# tiffany.net
KiCad netlist of a schematic drawn in EAGLE
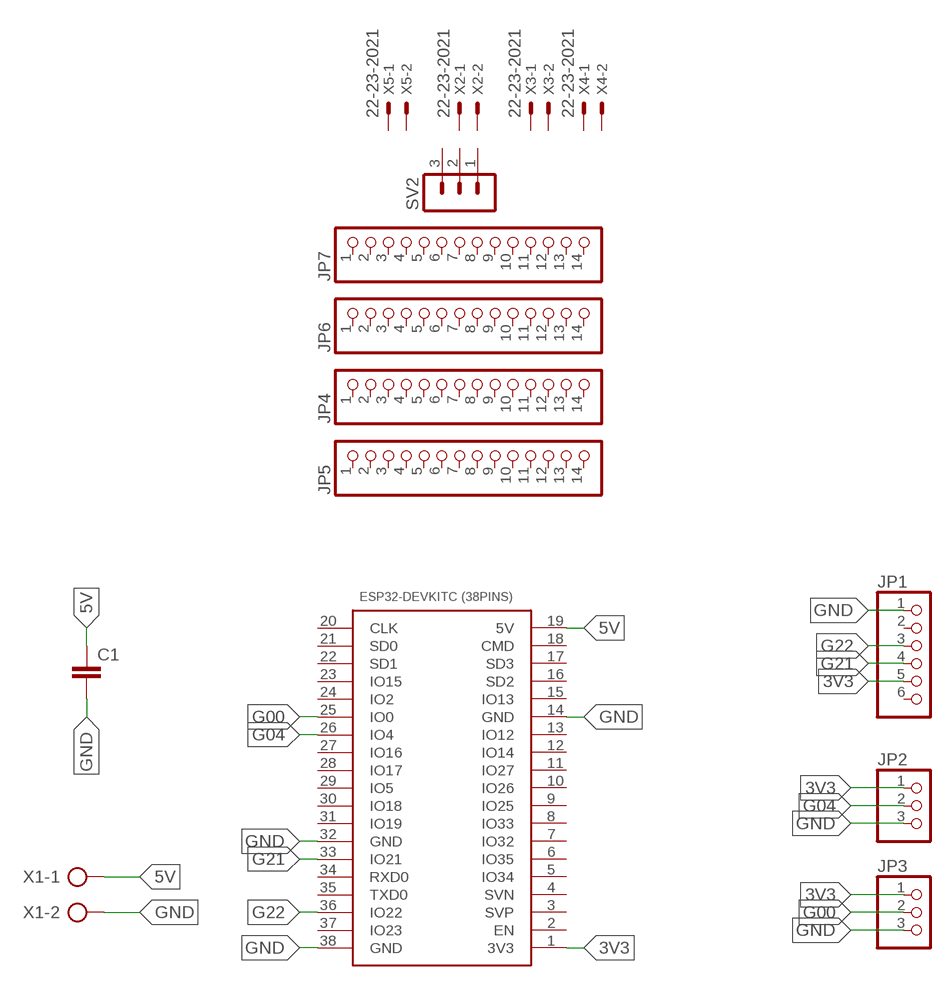
[diagram p0: schematic, sheet 1]

(export (version "E")
  (design (tool "Eeschema 10.0.6"))
  (components
    (comp (ref "C1")
      (value "C-EU050-024X044")
      (footprint "eagle-import:C050-024X044")
      (libsource (lib "eagle-import") (part "C-EU050-024X044"))
    )
    (comp (ref "ESP32-DEVKITC(38PINS)1")
      (value "ESP32DEVKITC_38PINS")
      (footprint "eagle-import:ESP32-DEVKITC")
      (libsource (lib "eagle-import") (part "ESP32DEVKITC_38PINS"))
    )
    (comp (ref "JP1")
      (value "PINHD-1X6")
      (footprint "eagle-import:1X06")
      (libsource (lib "eagle-import") (part "PINHD-1X6"))
    )
    (comp (ref "JP2")
      (value "PINHD-1X3")
      (footprint "eagle-import:1X03")
      (libsource (lib "eagle-import") (part "PINHD-1X3"))
    )
    (comp (ref "JP3")
      (value "PINHD-1X3")
      (footprint "eagle-import:1X03")
      (libsource (lib "eagle-import") (part "PINHD-1X3"))
    )
    (comp (ref "JP4")
      (value "PINHD-1X14")
      (footprint "eagle-import:1X14")
      (libsource (lib "eagle-import") (part "PINHD-1X14"))
    )
    (comp (ref "JP5")
      (value "PINHD-1X14")
      (footprint "eagle-import:1X14")
      (libsource (lib "eagle-import") (part "PINHD-1X14"))
    )
    (comp (ref "JP6")
      (value "PINHD-1X14")
      (footprint "eagle-import:1X14")
      (libsource (lib "eagle-import") (part "PINHD-1X14"))
    )
    (comp (ref "JP7")
      (value "PINHD-1X14")
      (footprint "eagle-import:1X14")
      (libsource (lib "eagle-import") (part "PINHD-1X14"))
    )
    (comp (ref "SV2")
      (value "MA03-1")
      (footprint "eagle-import:MA03-1")
      (libsource (lib "eagle-import") (part "MA03-1"))
    )
    (comp (ref "X1")
      (value "AK300/2")
      (footprint "eagle-import:AK300_2")
      (libsource (lib "eagle-import") (part "AK300/2"))
    )
    (comp (ref "X2")
      (value "22-23-2021")
      (footprint "eagle-import:22-23-2021")
      (fields (field (name "MF") "MOLEX"))
      (libsource (lib "eagle-import") (part "22-23-2021"))
    )
    (comp (ref "X3")
      (value "22-23-2021")
      (footprint "eagle-import:22-23-2021")
      (fields (field (name "MF") "MOLEX"))
      (libsource (lib "eagle-import") (part "22-23-2021"))
    )
    (comp (ref "X4")
      (value "22-23-2021")
      (footprint "eagle-import:22-23-2021")
      (fields (field (name "MF") "MOLEX"))
      (libsource (lib "eagle-import") (part "22-23-2021"))
    )
    (comp (ref "X5")
      (value "22-23-2021")
      (footprint "eagle-import:22-23-2021")
      (fields (field (name "MF") "MOLEX"))
      (libsource (lib "eagle-import") (part "22-23-2021"))
    )
  )
  (nets
    (net (code "1") (name "3V3") (class "Default")
      (node (ref "ESP32-DEVKITC(38PINS)1") (pin "1") (pinfunction "3V3_1") (pintype "bidirectional"))
      (node (ref "JP1") (pin "5") (pinfunction "5_5") (pintype "passive"))
      (node (ref "JP2") (pin "1") (pinfunction "1_1") (pintype "passive"))
      (node (ref "JP3") (pin "1") (pinfunction "1_1") (pintype "passive"))
    )
    (net (code "2") (name "5V") (class "Default")
      (node (ref "C1") (pin "1") (pinfunction "1_1") (pintype "passive"))
      (node (ref "ESP32-DEVKITC(38PINS)1") (pin "19") (pinfunction "5V_19") (pintype "bidirectional"))
      (node (ref "X1") (pin "1") (pinfunction "KL_1") (pintype "passive"))
    )
    (net (code "3") (name "G00") (class "Default")
      (node (ref "ESP32-DEVKITC(38PINS)1") (pin "25") (pinfunction "IO0_25") (pintype "bidirectional"))
      (node (ref "JP3") (pin "2") (pinfunction "2_2") (pintype "passive"))
    )
    (net (code "4") (name "G04") (class "Default")
      (node (ref "ESP32-DEVKITC(38PINS)1") (pin "26") (pinfunction "IO4_26") (pintype "bidirectional"))
      (node (ref "JP2") (pin "2") (pinfunction "2_2") (pintype "passive"))
    )
    (net (code "5") (name "G21") (class "Default")
      (node (ref "ESP32-DEVKITC(38PINS)1") (pin "33") (pinfunction "IO21_33") (pintype "bidirectional"))
      (node (ref "JP1") (pin "4") (pinfunction "4_4") (pintype "passive"))
    )
    (net (code "6") (name "G22") (class "Default")
      (node (ref "ESP32-DEVKITC(38PINS)1") (pin "36") (pinfunction "IO22_36") (pintype "bidirectional"))
      (node (ref "JP1") (pin "3") (pinfunction "3_3") (pintype "passive"))
    )
    (net (code "7") (name "GND") (class "Default")
      (node (ref "C1") (pin "2") (pinfunction "2_2") (pintype "passive"))
      (node (ref "ESP32-DEVKITC(38PINS)1") (pin "14") (pinfunction "GND_14") (pintype "bidirectional"))
      (node (ref "ESP32-DEVKITC(38PINS)1") (pin "32") (pinfunction "GND_32") (pintype "bidirectional"))
      (node (ref "ESP32-DEVKITC(38PINS)1") (pin "38") (pinfunction "GND_38") (pintype "bidirectional"))
      (node (ref "JP1") (pin "1") (pinfunction "1_1") (pintype "passive"))
      (node (ref "JP2") (pin "3") (pinfunction "3_3") (pintype "passive"))
      (node (ref "JP3") (pin "3") (pinfunction "3_3") (pintype "passive"))
      (node (ref "X1") (pin "2") (pinfunction "KL_2") (pintype "passive"))
    )
    (net (code "8") (name "unconnected-(ESP32-DEVKITC(38PINS)1-CLK-Pad20)") (class "Default")
      (node (ref "ESP32-DEVKITC(38PINS)1") (pin "20") (pinfunction "CLK_20") (pintype "bidirectional"))
    )
    (net (code "9") (name "unconnected-(ESP32-DEVKITC(38PINS)1-CMD-Pad18)") (class "Default")
      (node (ref "ESP32-DEVKITC(38PINS)1") (pin "18") (pinfunction "CMD_18") (pintype "bidirectional"))
    )
    (net (code "10") (name "unconnected-(ESP32-DEVKITC(38PINS)1-EN-Pad2)") (class "Default")
      (node (ref "ESP32-DEVKITC(38PINS)1") (pin "2") (pinfunction "EN_2") (pintype "bidirectional"))
    )
    (net (code "11") (name "unconnected-(ESP32-DEVKITC(38PINS)1-IO2-Pad24)") (class "Default")
      (node (ref "ESP32-DEVKITC(38PINS)1") (pin "24") (pinfunction "IO2_24") (pintype "bidirectional"))
    )
    (net (code "12") (name "unconnected-(ESP32-DEVKITC(38PINS)1-IO5-Pad29)") (class "Default")
      (node (ref "ESP32-DEVKITC(38PINS)1") (pin "29") (pinfunction "IO5_29") (pintype "bidirectional"))
    )
    (net (code "13") (name "unconnected-(ESP32-DEVKITC(38PINS)1-IO12-Pad13)") (class "Default")
      (node (ref "ESP32-DEVKITC(38PINS)1") (pin "13") (pinfunction "IO12_13") (pintype "bidirectional"))
    )
    (net (code "14") (name "unconnected-(ESP32-DEVKITC(38PINS)1-IO13-Pad15)") (class "Default")
      (node (ref "ESP32-DEVKITC(38PINS)1") (pin "15") (pinfunction "IO13_15") (pintype "bidirectional"))
    )
    (net (code "15") (name "unconnected-(ESP32-DEVKITC(38PINS)1-IO14-Pad12)") (class "Default")
      (node (ref "ESP32-DEVKITC(38PINS)1") (pin "12") (pinfunction "IO14_12") (pintype "bidirectional"))
    )
    (net (code "16") (name "unconnected-(ESP32-DEVKITC(38PINS)1-IO15-Pad23)") (class "Default")
      (node (ref "ESP32-DEVKITC(38PINS)1") (pin "23") (pinfunction "IO15_23") (pintype "bidirectional"))
    )
    (net (code "17") (name "unconnected-(ESP32-DEVKITC(38PINS)1-IO16-Pad27)") (class "Default")
      (node (ref "ESP32-DEVKITC(38PINS)1") (pin "27") (pinfunction "IO16_27") (pintype "bidirectional"))
    )
    (net (code "18") (name "unconnected-(ESP32-DEVKITC(38PINS)1-IO17-Pad28)") (class "Default")
      (node (ref "ESP32-DEVKITC(38PINS)1") (pin "28") (pinfunction "IO17_28") (pintype "bidirectional"))
    )
    (net (code "19") (name "unconnected-(ESP32-DEVKITC(38PINS)1-IO18-Pad30)") (class "Default")
      (node (ref "ESP32-DEVKITC(38PINS)1") (pin "30") (pinfunction "IO18_30") (pintype "bidirectional"))
    )
    (net (code "20") (name "unconnected-(ESP32-DEVKITC(38PINS)1-IO19-Pad31)") (class "Default")
      (node (ref "ESP32-DEVKITC(38PINS)1") (pin "31") (pinfunction "IO19_31") (pintype "bidirectional"))
    )
    (net (code "21") (name "unconnected-(ESP32-DEVKITC(38PINS)1-IO23-Pad37)") (class "Default")
      (node (ref "ESP32-DEVKITC(38PINS)1") (pin "37") (pinfunction "IO23_37") (pintype "bidirectional"))
    )
    (net (code "22") (name "unconnected-(ESP32-DEVKITC(38PINS)1-IO25-Pad9)") (class "Default")
      (node (ref "ESP32-DEVKITC(38PINS)1") (pin "9") (pinfunction "IO25_9") (pintype "bidirectional"))
    )
    (net (code "23") (name "unconnected-(ESP32-DEVKITC(38PINS)1-IO26-Pad10)") (class "Default")
      (node (ref "ESP32-DEVKITC(38PINS)1") (pin "10") (pinfunction "IO26_10") (pintype "bidirectional"))
    )
    (net (code "24") (name "unconnected-(ESP32-DEVKITC(38PINS)1-IO27-Pad11)") (class "Default")
      (node (ref "ESP32-DEVKITC(38PINS)1") (pin "11") (pinfunction "IO27_11") (pintype "bidirectional"))
    )
    (net (code "25") (name "unconnected-(ESP32-DEVKITC(38PINS)1-IO32-Pad7)") (class "Default")
      (node (ref "ESP32-DEVKITC(38PINS)1") (pin "7") (pinfunction "IO32_7") (pintype "bidirectional"))
    )
    (net (code "26") (name "unconnected-(ESP32-DEVKITC(38PINS)1-IO33-Pad8)") (class "Default")
      (node (ref "ESP32-DEVKITC(38PINS)1") (pin "8") (pinfunction "IO33_8") (pintype "bidirectional"))
    )
    (net (code "27") (name "unconnected-(ESP32-DEVKITC(38PINS)1-IO34-Pad5)") (class "Default")
      (node (ref "ESP32-DEVKITC(38PINS)1") (pin "5") (pinfunction "IO34_5") (pintype "bidirectional"))
    )
    (net (code "28") (name "unconnected-(ESP32-DEVKITC(38PINS)1-IO35-Pad6)") (class "Default")
      (node (ref "ESP32-DEVKITC(38PINS)1") (pin "6") (pinfunction "IO35_6") (pintype "bidirectional"))
    )
    (net (code "29") (name "unconnected-(ESP32-DEVKITC(38PINS)1-RXD0-Pad34)") (class "Default")
      (node (ref "ESP32-DEVKITC(38PINS)1") (pin "34") (pinfunction "RXD0_34") (pintype "bidirectional"))
    )
    (net (code "30") (name "unconnected-(ESP32-DEVKITC(38PINS)1-SD0-Pad21)") (class "Default")
      (node (ref "ESP32-DEVKITC(38PINS)1") (pin "21") (pinfunction "SD0_21") (pintype "bidirectional"))
    )
    (net (code "31") (name "unconnected-(ESP32-DEVKITC(38PINS)1-SD1-Pad22)") (class "Default")
      (node (ref "ESP32-DEVKITC(38PINS)1") (pin "22") (pinfunction "SD1_22") (pintype "bidirectional"))
    )
    (net (code "32") (name "unconnected-(ESP32-DEVKITC(38PINS)1-SD2-Pad16)") (class "Default")
      (node (ref "ESP32-DEVKITC(38PINS)1") (pin "16") (pinfunction "SD2_16") (pintype "bidirectional"))
    )
    (net (code "33") (name "unconnected-(ESP32-DEVKITC(38PINS)1-SD3-Pad17)") (class "Default")
      (node (ref "ESP32-DEVKITC(38PINS)1") (pin "17") (pinfunction "SD3_17") (pintype "bidirectional"))
    )
    (net (code "34") (name "unconnected-(ESP32-DEVKITC(38PINS)1-SVN-Pad4)") (class "Default")
      (node (ref "ESP32-DEVKITC(38PINS)1") (pin "4") (pinfunction "SVN_4") (pintype "bidirectional"))
    )
    (net (code "35") (name "unconnected-(ESP32-DEVKITC(38PINS)1-SVP-Pad3)") (class "Default")
      (node (ref "ESP32-DEVKITC(38PINS)1") (pin "3") (pinfunction "SVP_3") (pintype "bidirectional"))
    )
    (net (code "36") (name "unconnected-(ESP32-DEVKITC(38PINS)1-TXD0-Pad35)") (class "Default")
      (node (ref "ESP32-DEVKITC(38PINS)1") (pin "35") (pinfunction "TXD0_35") (pintype "bidirectional"))
    )
    (net (code "37") (name "unconnected-(JP1-Pad2)") (class "Default")
      (node (ref "JP1") (pin "2") (pinfunction "2_2") (pintype "passive"))
    )
    (net (code "38") (name "unconnected-(JP1-Pad6)") (class "Default")
      (node (ref "JP1") (pin "6") (pinfunction "6_6") (pintype "passive"))
    )
    (net (code "39") (name "unconnected-(JP4-Pad1)") (class "Default")
      (node (ref "JP4") (pin "1") (pinfunction "1_1") (pintype "passive"))
    )
    (net (code "40") (name "unconnected-(JP4-Pad2)") (class "Default")
      (node (ref "JP4") (pin "2") (pinfunction "2_2") (pintype "passive"))
    )
    (net (code "41") (name "unconnected-(JP4-Pad3)") (class "Default")
      (node (ref "JP4") (pin "3") (pinfunction "3_3") (pintype "passive"))
    )
    (net (code "42") (name "unconnected-(JP4-Pad4)") (class "Default")
      (node (ref "JP4") (pin "4") (pinfunction "4_4") (pintype "passive"))
    )
    (net (code "43") (name "unconnected-(JP4-Pad5)") (class "Default")
      (node (ref "JP4") (pin "5") (pinfunction "5_5") (pintype "passive"))
    )
    (net (code "44") (name "unconnected-(JP4-Pad6)") (class "Default")
      (node (ref "JP4") (pin "6") (pinfunction "6_6") (pintype "passive"))
    )
    (net (code "45") (name "unconnected-(JP4-Pad7)") (class "Default")
      (node (ref "JP4") (pin "7") (pinfunction "7_7") (pintype "passive"))
    )
    (net (code "46") (name "unconnected-(JP4-Pad8)") (class "Default")
      (node (ref "JP4") (pin "8") (pinfunction "8_8") (pintype "passive"))
    )
    (net (code "47") (name "unconnected-(JP4-Pad9)") (class "Default")
      (node (ref "JP4") (pin "9") (pinfunction "9_9") (pintype "passive"))
    )
    (net (code "48") (name "unconnected-(JP4-Pad10)") (class "Default")
      (node (ref "JP4") (pin "10") (pinfunction "10_10") (pintype "passive"))
    )
    (net (code "49") (name "unconnected-(JP4-Pad11)") (class "Default")
      (node (ref "JP4") (pin "11") (pinfunction "11_11") (pintype "passive"))
    )
    (net (code "50") (name "unconnected-(JP4-Pad12)") (class "Default")
      (node (ref "JP4") (pin "12") (pinfunction "12_12") (pintype "passive"))
    )
    (net (code "51") (name "unconnected-(JP4-Pad13)") (class "Default")
      (node (ref "JP4") (pin "13") (pinfunction "13_13") (pintype "passive"))
    )
    (net (code "52") (name "unconnected-(JP4-Pad14)") (class "Default")
      (node (ref "JP4") (pin "14") (pinfunction "14_14") (pintype "passive"))
    )
    (net (code "53") (name "unconnected-(JP5-Pad1)") (class "Default")
      (node (ref "JP5") (pin "1") (pinfunction "1_1") (pintype "passive"))
    )
    (net (code "54") (name "unconnected-(JP5-Pad2)") (class "Default")
      (node (ref "JP5") (pin "2") (pinfunction "2_2") (pintype "passive"))
    )
    (net (code "55") (name "unconnected-(JP5-Pad3)") (class "Default")
      (node (ref "JP5") (pin "3") (pinfunction "3_3") (pintype "passive"))
    )
    (net (code "56") (name "unconnected-(JP5-Pad4)") (class "Default")
      (node (ref "JP5") (pin "4") (pinfunction "4_4") (pintype "passive"))
    )
    (net (code "57") (name "unconnected-(JP5-Pad5)") (class "Default")
      (node (ref "JP5") (pin "5") (pinfunction "5_5") (pintype "passive"))
    )
    (net (code "58") (name "unconnected-(JP5-Pad6)") (class "Default")
      (node (ref "JP5") (pin "6") (pinfunction "6_6") (pintype "passive"))
    )
    (net (code "59") (name "unconnected-(JP5-Pad7)") (class "Default")
      (node (ref "JP5") (pin "7") (pinfunction "7_7") (pintype "passive"))
    )
    (net (code "60") (name "unconnected-(JP5-Pad8)") (class "Default")
      (node (ref "JP5") (pin "8") (pinfunction "8_8") (pintype "passive"))
    )
    (net (code "61") (name "unconnected-(JP5-Pad9)") (class "Default")
      (node (ref "JP5") (pin "9") (pinfunction "9_9") (pintype "passive"))
    )
    (net (code "62") (name "unconnected-(JP5-Pad10)") (class "Default")
      (node (ref "JP5") (pin "10") (pinfunction "10_10") (pintype "passive"))
    )
    (net (code "63") (name "unconnected-(JP5-Pad11)") (class "Default")
      (node (ref "JP5") (pin "11") (pinfunction "11_11") (pintype "passive"))
    )
    (net (code "64") (name "unconnected-(JP5-Pad12)") (class "Default")
      (node (ref "JP5") (pin "12") (pinfunction "12_12") (pintype "passive"))
    )
    (net (code "65") (name "unconnected-(JP5-Pad13)") (class "Default")
      (node (ref "JP5") (pin "13") (pinfunction "13_13") (pintype "passive"))
    )
    (net (code "66") (name "unconnected-(JP5-Pad14)") (class "Default")
      (node (ref "JP5") (pin "14") (pinfunction "14_14") (pintype "passive"))
    )
    (net (code "67") (name "unconnected-(JP6-Pad1)") (class "Default")
      (node (ref "JP6") (pin "1") (pinfunction "1_1") (pintype "passive"))
    )
    (net (code "68") (name "unconnected-(JP6-Pad2)") (class "Default")
      (node (ref "JP6") (pin "2") (pinfunction "2_2") (pintype "passive"))
    )
    (net (code "69") (name "unconnected-(JP6-Pad3)") (class "Default")
      (node (ref "JP6") (pin "3") (pinfunction "3_3") (pintype "passive"))
    )
    (net (code "70") (name "unconnected-(JP6-Pad4)") (class "Default")
      (node (ref "JP6") (pin "4") (pinfunction "4_4") (pintype "passive"))
    )
    (net (code "71") (name "unconnected-(JP6-Pad5)") (class "Default")
      (node (ref "JP6") (pin "5") (pinfunction "5_5") (pintype "passive"))
    )
    (net (code "72") (name "unconnected-(JP6-Pad6)") (class "Default")
      (node (ref "JP6") (pin "6") (pinfunction "6_6") (pintype "passive"))
    )
    (net (code "73") (name "unconnected-(JP6-Pad7)") (class "Default")
      (node (ref "JP6") (pin "7") (pinfunction "7_7") (pintype "passive"))
    )
    (net (code "74") (name "unconnected-(JP6-Pad8)") (class "Default")
      (node (ref "JP6") (pin "8") (pinfunction "8_8") (pintype "passive"))
    )
    (net (code "75") (name "unconnected-(JP6-Pad9)") (class "Default")
      (node (ref "JP6") (pin "9") (pinfunction "9_9") (pintype "passive"))
    )
    (net (code "76") (name "unconnected-(JP6-Pad10)") (class "Default")
      (node (ref "JP6") (pin "10") (pinfunction "10_10") (pintype "passive"))
    )
    (net (code "77") (name "unconnected-(JP6-Pad11)") (class "Default")
      (node (ref "JP6") (pin "11") (pinfunction "11_11") (pintype "passive"))
    )
    (net (code "78") (name "unconnected-(JP6-Pad12)") (class "Default")
      (node (ref "JP6") (pin "12") (pinfunction "12_12") (pintype "passive"))
    )
    (net (code "79") (name "unconnected-(JP6-Pad13)") (class "Default")
      (node (ref "JP6") (pin "13") (pinfunction "13_13") (pintype "passive"))
    )
    (net (code "80") (name "unconnected-(JP6-Pad14)") (class "Default")
      (node (ref "JP6") (pin "14") (pinfunction "14_14") (pintype "passive"))
    )
    (net (code "81") (name "unconnected-(JP7-Pad1)") (class "Default")
      (node (ref "JP7") (pin "1") (pinfunction "1_1") (pintype "passive"))
    )
    (net (code "82") (name "unconnected-(JP7-Pad2)") (class "Default")
      (node (ref "JP7") (pin "2") (pinfunction "2_2") (pintype "passive"))
    )
    (net (code "83") (name "unconnected-(JP7-Pad3)") (class "Default")
      (node (ref "JP7") (pin "3") (pinfunction "3_3") (pintype "passive"))
    )
    (net (code "84") (name "unconnected-(JP7-Pad4)") (class "Default")
      (node (ref "JP7") (pin "4") (pinfunction "4_4") (pintype "passive"))
    )
    (net (code "85") (name "unconnected-(JP7-Pad5)") (class "Default")
      (node (ref "JP7") (pin "5") (pinfunction "5_5") (pintype "passive"))
    )
    (net (code "86") (name "unconnected-(JP7-Pad6)") (class "Default")
      (node (ref "JP7") (pin "6") (pinfunction "6_6") (pintype "passive"))
    )
    (net (code "87") (name "unconnected-(JP7-Pad7)") (class "Default")
      (node (ref "JP7") (pin "7") (pinfunction "7_7") (pintype "passive"))
    )
    (net (code "88") (name "unconnected-(JP7-Pad8)") (class "Default")
      (node (ref "JP7") (pin "8") (pinfunction "8_8") (pintype "passive"))
    )
    (net (code "89") (name "unconnected-(JP7-Pad9)") (class "Default")
      (node (ref "JP7") (pin "9") (pinfunction "9_9") (pintype "passive"))
    )
    (net (code "90") (name "unconnected-(JP7-Pad10)") (class "Default")
      (node (ref "JP7") (pin "10") (pinfunction "10_10") (pintype "passive"))
    )
    (net (code "91") (name "unconnected-(JP7-Pad11)") (class "Default")
      (node (ref "JP7") (pin "11") (pinfunction "11_11") (pintype "passive"))
    )
    (net (code "92") (name "unconnected-(JP7-Pad12)") (class "Default")
      (node (ref "JP7") (pin "12") (pinfunction "12_12") (pintype "passive"))
    )
    (net (code "93") (name "unconnected-(JP7-Pad13)") (class "Default")
      (node (ref "JP7") (pin "13") (pinfunction "13_13") (pintype "passive"))
    )
    (net (code "94") (name "unconnected-(JP7-Pad14)") (class "Default")
      (node (ref "JP7") (pin "14") (pinfunction "14_14") (pintype "passive"))
    )
    (net (code "95") (name "unconnected-(SV2-Pad1)") (class "Default")
      (node (ref "SV2") (pin "1") (pinfunction "1_1") (pintype "passive"))
    )
    (net (code "96") (name "unconnected-(SV2-Pad2)") (class "Default")
      (node (ref "SV2") (pin "2") (pinfunction "2_2") (pintype "passive"))
    )
    (net (code "97") (name "unconnected-(SV2-Pad3)") (class "Default")
      (node (ref "SV2") (pin "3") (pinfunction "3_3") (pintype "passive"))
    )
    (net (code "98") (name "unconnected-(X2A-S-Pad1)") (class "Default")
      (node (ref "X2") (pin "1") (pinfunction "S_1") (pintype "passive"))
    )
    (net (code "99") (name "unconnected-(X2B-S-Pad2)") (class "Default")
      (node (ref "X2") (pin "2") (pinfunction "S_2") (pintype "passive"))
    )
    (net (code "100") (name "unconnected-(X3A-S-Pad1)") (class "Default")
      (node (ref "X3") (pin "1") (pinfunction "S_1") (pintype "passive"))
    )
    (net (code "101") (name "unconnected-(X3B-S-Pad2)") (class "Default")
      (node (ref "X3") (pin "2") (pinfunction "S_2") (pintype "passive"))
    )
    (net (code "102") (name "unconnected-(X4A-S-Pad1)") (class "Default")
      (node (ref "X4") (pin "1") (pinfunction "S_1") (pintype "passive"))
    )
    (net (code "103") (name "unconnected-(X4B-S-Pad2)") (class "Default")
      (node (ref "X4") (pin "2") (pinfunction "S_2") (pintype "passive"))
    )
    (net (code "104") (name "unconnected-(X5A-S-Pad1)") (class "Default")
      (node (ref "X5") (pin "1") (pinfunction "S_1") (pintype "passive"))
    )
    (net (code "105") (name "unconnected-(X5B-S-Pad2)") (class "Default")
      (node (ref "X5") (pin "2") (pinfunction "S_2") (pintype "passive"))
    )
  )
)
